# mobo_v2_0_6-20-18.net
KiCad netlist of a schematic drawn in EAGLE
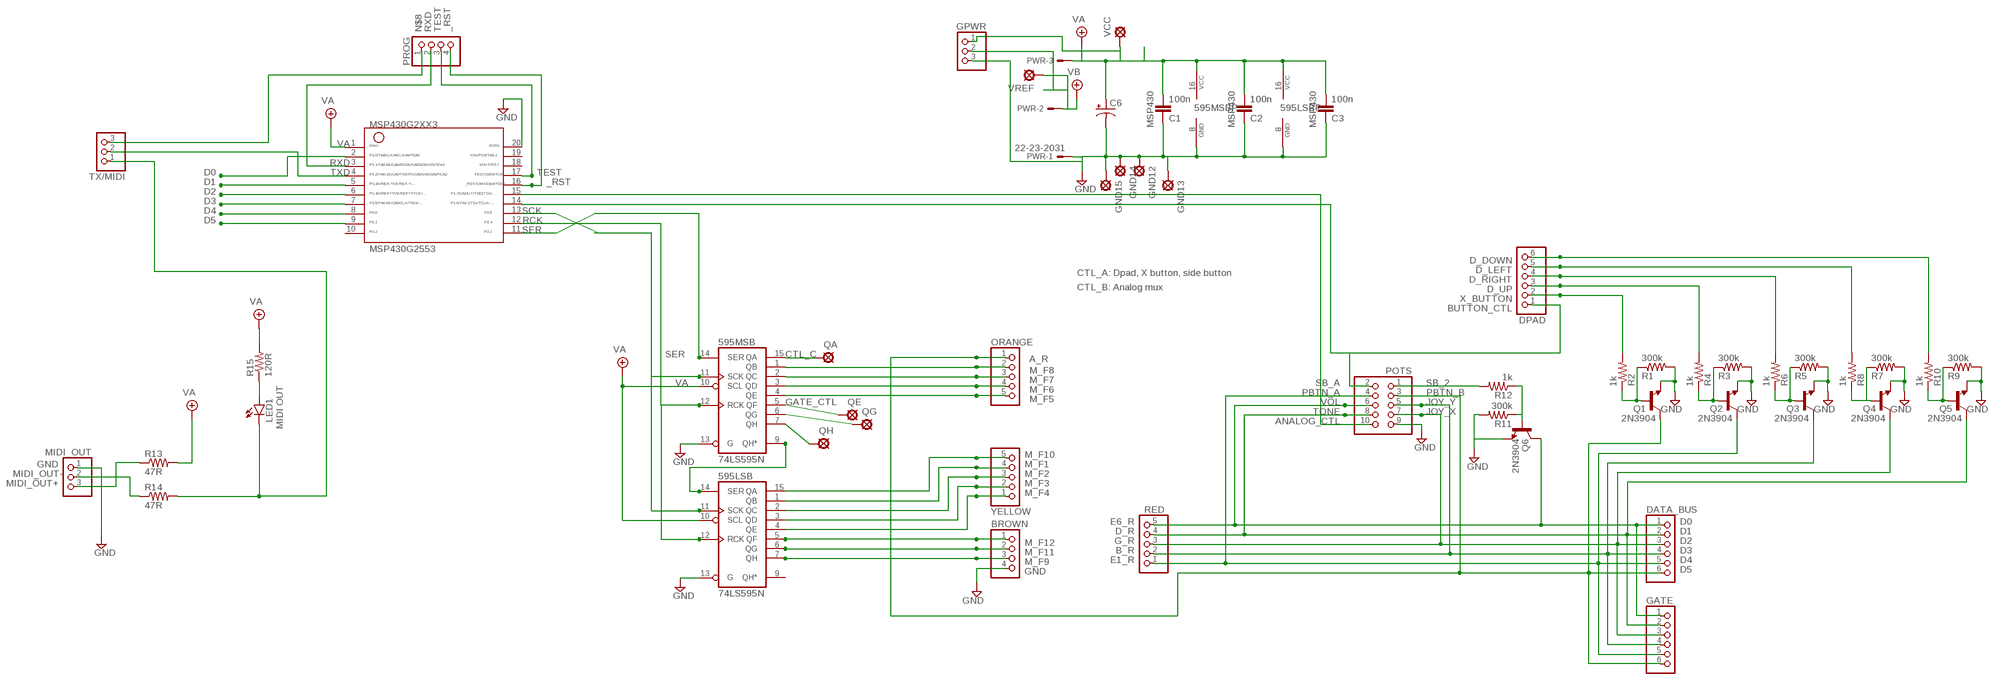
[diagram p0: schematic, sheet 1]

(export (version "E")
  (design (tool "Eeschema 10.0.6"))
  (components
    (comp (ref "595LSB")
      (value "74LS595N")
      (footprint "eagle-import:DIL16")
      (libsource (lib "eagle-import") (part "74595NLS"))
    )
    (comp (ref "595MSB")
      (value "74LS595N")
      (footprint "eagle-import:DIL16")
      (libsource (lib "eagle-import") (part "74595NLS"))
    )
    (comp (ref "BROWN")
      (value "PINHD-1X4")
      (footprint "eagle-import:1X04")
      (libsource (lib "eagle-import") (part "PINHD-1X4"))
    )
    (comp (ref "C1")
      (value "100n")
      (footprint "eagle-import:050X030_050_3")
      (libsource (lib "eagle-import") (part "050X030_050"))
    )
    (comp (ref "C2")
      (value "100n")
      (footprint "eagle-import:050X030_050_1")
      (libsource (lib "eagle-import") (part "050X030_0501"))
    )
    (comp (ref "C3")
      (value "100n")
      (footprint "eagle-import:050X030_050_1")
      (libsource (lib "eagle-import") (part "050X030_0501"))
    )
    (comp (ref "C6")
      (value "0501")
      (footprint "eagle-import:050_020_1")
      (libsource (lib "eagle-import") (part "0501"))
    )
    (comp (ref "DATA_BUS")
      (value "PINHD-1X6")
      (footprint "eagle-import:1X06")
      (libsource (lib "eagle-import") (part "PINHD-1X6"))
    )
    (comp (ref "DPAD")
      (value "PINHD-1X6")
      (footprint "eagle-import:1X06")
      (libsource (lib "eagle-import") (part "PINHD-1X6"))
    )
    (comp (ref "GATE")
      (value "PINHD-1X6")
      (footprint "eagle-import:1X06")
      (libsource (lib "eagle-import") (part "PINHD-1X6"))
    )
    (comp (ref "GND12")
      (value "PAD")
      (footprint "eagle-import:SQUARE")
      (libsource (lib "eagle-import") (part "PAD"))
    )
    (comp (ref "GND13")
      (value "PAD")
      (footprint "eagle-import:SQUARE")
      (libsource (lib "eagle-import") (part "PAD"))
    )
    (comp (ref "GND14")
      (value "PAD")
      (footprint "eagle-import:SQUARE")
      (libsource (lib "eagle-import") (part "PAD"))
    )
    (comp (ref "GND15")
      (value "PAD")
      (footprint "eagle-import:SQUARE")
      (libsource (lib "eagle-import") (part "PAD"))
    )
    (comp (ref "GPWR")
      (value "PINHD-1X3")
      (footprint "eagle-import:1X03")
      (libsource (lib "eagle-import") (part "PINHD-1X3"))
    )
    (comp (ref "LED1")
      (value "LED3MM")
      (footprint "eagle-import:LED3MM")
      (libsource (lib "eagle-import") (part "LED3MM"))
    )
    (comp (ref "MIDI_OUT")
      (value "PINHD-1X3")
      (footprint "eagle-import:1X03")
      (libsource (lib "eagle-import") (part "PINHD-1X3"))
    )
    (comp (ref "MSP430G2553")
      (value "G2XX3---N20")
      (footprint "eagle-import:N20")
      (libsource (lib "eagle-import") (part "G2XX3---N20"))
    )
    (comp (ref "ORANGE")
      (value "PINHD-1X5")
      (footprint "eagle-import:1X05")
      (libsource (lib "eagle-import") (part "PINHD-1X5"))
    )
    (comp (ref "POTS")
      (value "PINHD-2X5IDC")
      (footprint "eagle-import:10PIN_IDC")
      (libsource (lib "eagle-import") (part "PINHD-2X5IDC"))
    )
    (comp (ref "PROG")
      (value "PINHD-1X4")
      (footprint "eagle-import:1X04")
      (libsource (lib "eagle-import") (part "PINHD-1X4"))
    )
    (comp (ref "PWR")
      (value "22-23-2031")
      (footprint "eagle-import:22-23-2031")
      (fields (field (name "MF") "MOLEX"))
      (libsource (lib "eagle-import") (part "22-23-2031"))
    )
    (comp (ref "Q1")
      (value "2N3904")
      (footprint "eagle-import:TO92-")
      (libsource (lib "eagle-import") (part "2N3904"))
    )
    (comp (ref "Q2")
      (value "2N3904")
      (footprint "eagle-import:TO92-")
      (libsource (lib "eagle-import") (part "2N3904"))
    )
    (comp (ref "Q3")
      (value "2N3904")
      (footprint "eagle-import:TO92-")
      (libsource (lib "eagle-import") (part "2N3904"))
    )
    (comp (ref "Q4")
      (value "2N3904")
      (footprint "eagle-import:TO92-")
      (libsource (lib "eagle-import") (part "2N3904"))
    )
    (comp (ref "Q5")
      (value "2N3904")
      (footprint "eagle-import:TO92-")
      (libsource (lib "eagle-import") (part "2N3904"))
    )
    (comp (ref "Q6")
      (value "2N3904")
      (footprint "eagle-import:TO92-")
      (libsource (lib "eagle-import") (part "2N3904"))
    )
    (comp (ref "QA")
      (value "PAD")
      (footprint "eagle-import:SQUARE")
      (libsource (lib "eagle-import") (part "PAD"))
    )
    (comp (ref "QE")
      (value "PAD")
      (footprint "eagle-import:SQUARE")
      (libsource (lib "eagle-import") (part "PAD"))
    )
    (comp (ref "QG")
      (value "PAD")
      (footprint "eagle-import:SQUARE")
      (libsource (lib "eagle-import") (part "PAD"))
    )
    (comp (ref "QH")
      (value "PAD")
      (footprint "eagle-import:SQUARE")
      (libsource (lib "eagle-import") (part "PAD"))
    )
    (comp (ref "R1")
      (value "300k")
      (footprint "eagle-import:R0207_3")
      (libsource (lib "eagle-import") (part "6MM.3"))
    )
    (comp (ref "R2")
      (value "1k")
      (footprint "eagle-import:R0207_3")
      (libsource (lib "eagle-import") (part "6MM.3"))
    )
    (comp (ref "R3")
      (value "300k")
      (footprint "eagle-import:R0207_3")
      (libsource (lib "eagle-import") (part "6MM.3"))
    )
    (comp (ref "R4")
      (value "1k")
      (footprint "eagle-import:R0207_3")
      (libsource (lib "eagle-import") (part "6MM.3"))
    )
    (comp (ref "R5")
      (value "300k")
      (footprint "eagle-import:R0207_3")
      (libsource (lib "eagle-import") (part "6MM.3"))
    )
    (comp (ref "R6")
      (value "1k")
      (footprint "eagle-import:R0207_3")
      (libsource (lib "eagle-import") (part "6MM.3"))
    )
    (comp (ref "R7")
      (value "300k")
      (footprint "eagle-import:R0207_3")
      (libsource (lib "eagle-import") (part "6MM.3"))
    )
    (comp (ref "R8")
      (value "1k")
      (footprint "eagle-import:R0207_3")
      (libsource (lib "eagle-import") (part "6MM.3"))
    )
    (comp (ref "R9")
      (value "300k")
      (footprint "eagle-import:R0207_3")
      (libsource (lib "eagle-import") (part "6MM.3"))
    )
    (comp (ref "R10")
      (value "1k")
      (footprint "eagle-import:R0207_3")
      (libsource (lib "eagle-import") (part "6MM.3"))
    )
    (comp (ref "R11")
      (value "300k")
      (footprint "eagle-import:R0207_3")
      (libsource (lib "eagle-import") (part "6MM.3"))
    )
    (comp (ref "R12")
      (value "1k")
      (footprint "eagle-import:R0207_3")
      (libsource (lib "eagle-import") (part "6MM.3"))
    )
    (comp (ref "R13")
      (value "47R")
      (footprint "eagle-import:R0207_3")
      (libsource (lib "eagle-import") (part "6MM.3"))
    )
    (comp (ref "R14")
      (value "47R")
      (footprint "eagle-import:R0207_3")
      (libsource (lib "eagle-import") (part "6MM.3"))
    )
    (comp (ref "R15")
      (value "120R")
      (footprint "eagle-import:R0207_3")
      (libsource (lib "eagle-import") (part "6MM.3"))
    )
    (comp (ref "RED")
      (value "PINHD-1X5")
      (footprint "eagle-import:1X05")
      (libsource (lib "eagle-import") (part "PINHD-1X5"))
    )
    (comp (ref "TX/MIDI")
      (value "PINHD-1X3")
      (footprint "eagle-import:1X03")
      (libsource (lib "eagle-import") (part "PINHD-1X3"))
    )
    (comp (ref "VCC")
      (value "PAD")
      (footprint "eagle-import:SQUARE")
      (libsource (lib "eagle-import") (part "PAD"))
    )
    (comp (ref "VREF")
      (value "PAD")
      (footprint "eagle-import:SQUARE")
      (libsource (lib "eagle-import") (part "PAD"))
    )
    (comp (ref "YELLOW")
      (value "PINHD-1X5")
      (footprint "eagle-import:1X05")
      (libsource (lib "eagle-import") (part "PINHD-1X5"))
    )
  )
  (nets
    (net (code "1") (name "/ANALOG_CTL") (class "Default")
      (node (ref "MSP430G2553") (pin "15") (pinfunction "15_15") (pintype "bidirectional"))
      (node (ref "POTS") (pin "10") (pinfunction "10_10") (pintype "passive"))
    )
    (net (code "2") (name "/BUTTON_CTL") (class "Default")
      (node (ref "DPAD") (pin "1") (pinfunction "1_1") (pintype "passive"))
      (node (ref "MSP430G2553") (pin "14") (pinfunction "14_14") (pintype "bidirectional"))
      (node (ref "POTS") (pin "2") (pinfunction "2_2") (pintype "passive"))
    )
    (net (code "3") (name "/CTL_C") (class "Default")
      (node (ref "595MSB") (pin "15") (pinfunction "QA_15") (pintype "tri_state"))
      (node (ref "QA") (pin "1") (pinfunction "PAD_1") (pintype "passive"))
    )
    (net (code "4") (name "/D0") (class "Default")
      (node (ref "DATA_BUS") (pin "1") (pinfunction "1_1") (pintype "passive"))
      (node (ref "GATE") (pin "1") (pinfunction "1_1") (pintype "passive"))
      (node (ref "MSP430G2553") (pin "2") (pinfunction "2_2") (pintype "bidirectional"))
      (node (ref "POTS") (pin "6") (pinfunction "6_6") (pintype "passive"))
      (node (ref "Q6") (pin "1") (pinfunction "C_1") (pintype "passive"))
      (node (ref "RED") (pin "5") (pinfunction "5_5") (pintype "passive"))
    )
    (net (code "5") (name "/D1") (class "Default")
      (node (ref "DATA_BUS") (pin "2") (pinfunction "2_2") (pintype "passive"))
      (node (ref "GATE") (pin "2") (pinfunction "2_2") (pintype "passive"))
      (node (ref "MSP430G2553") (pin "5") (pinfunction "5_5") (pintype "bidirectional"))
      (node (ref "POTS") (pin "8") (pinfunction "8_8") (pintype "passive"))
      (node (ref "Q5") (pin "1") (pinfunction "C_1") (pintype "passive"))
      (node (ref "RED") (pin "4") (pinfunction "4_4") (pintype "passive"))
    )
    (net (code "6") (name "/D2") (class "Default")
      (node (ref "DATA_BUS") (pin "3") (pinfunction "3_3") (pintype "passive"))
      (node (ref "GATE") (pin "3") (pinfunction "3_3") (pintype "passive"))
      (node (ref "MSP430G2553") (pin "6") (pinfunction "6_6") (pintype "bidirectional"))
      (node (ref "POTS") (pin "7") (pinfunction "7_7") (pintype "passive"))
      (node (ref "Q4") (pin "1") (pinfunction "C_1") (pintype "passive"))
      (node (ref "RED") (pin "3") (pinfunction "3_3") (pintype "passive"))
    )
    (net (code "7") (name "/D3") (class "Default")
      (node (ref "DATA_BUS") (pin "4") (pinfunction "4_4") (pintype "passive"))
      (node (ref "GATE") (pin "4") (pinfunction "4_4") (pintype "passive"))
      (node (ref "MSP430G2553") (pin "7") (pinfunction "7_7") (pintype "bidirectional"))
      (node (ref "POTS") (pin "5") (pinfunction "5_5") (pintype "passive"))
      (node (ref "Q3") (pin "1") (pinfunction "C_1") (pintype "passive"))
      (node (ref "RED") (pin "2") (pinfunction "2_2") (pintype "passive"))
    )
    (net (code "8") (name "/D4") (class "Default")
      (node (ref "DATA_BUS") (pin "5") (pinfunction "5_5") (pintype "passive"))
      (node (ref "GATE") (pin "5") (pinfunction "5_5") (pintype "passive"))
      (node (ref "MSP430G2553") (pin "8") (pinfunction "8_8") (pintype "bidirectional"))
      (node (ref "POTS") (pin "4") (pinfunction "4_4") (pintype "passive"))
      (node (ref "Q2") (pin "1") (pinfunction "C_1") (pintype "passive"))
      (node (ref "RED") (pin "1") (pinfunction "1_1") (pintype "passive"))
    )
    (net (code "9") (name "/D5") (class "Default")
      (node (ref "DATA_BUS") (pin "6") (pinfunction "6_6") (pintype "passive"))
      (node (ref "GATE") (pin "6") (pinfunction "6_6") (pintype "passive"))
      (node (ref "MSP430G2553") (pin "9") (pinfunction "9_9") (pintype "bidirectional"))
      (node (ref "ORANGE") (pin "1") (pinfunction "1_1") (pintype "passive"))
      (node (ref "POTS") (pin "3") (pinfunction "3_3") (pintype "passive"))
      (node (ref "Q1") (pin "1") (pinfunction "C_1") (pintype "passive"))
    )
    (net (code "10") (name "/D_DOWN") (class "Default")
      (node (ref "DPAD") (pin "6") (pinfunction "6_6") (pintype "passive"))
      (node (ref "R10") (pin "2") (pinfunction "2_2") (pintype "passive"))
    )
    (net (code "11") (name "/D_LEFT") (class "Default")
      (node (ref "DPAD") (pin "5") (pinfunction "5_5") (pintype "passive"))
      (node (ref "R8") (pin "2") (pinfunction "2_2") (pintype "passive"))
    )
    (net (code "12") (name "/D_RIGHT") (class "Default")
      (node (ref "DPAD") (pin "4") (pinfunction "4_4") (pintype "passive"))
      (node (ref "R6") (pin "2") (pinfunction "2_2") (pintype "passive"))
    )
    (net (code "13") (name "/D_UP") (class "Default")
      (node (ref "DPAD") (pin "3") (pinfunction "3_3") (pintype "passive"))
      (node (ref "R4") (pin "2") (pinfunction "2_2") (pintype "passive"))
    )
    (net (code "14") (name "/GATE_CTL") (class "Default")
      (node (ref "595MSB") (pin "5") (pinfunction "QF_5") (pintype "tri_state"))
      (node (ref "QE") (pin "1") (pinfunction "PAD_1") (pintype "passive"))
    )
    (net (code "15") (name "/MIDI_OUT+") (class "Default")
      (node (ref "MIDI_OUT") (pin "3") (pinfunction "3_3") (pintype "passive"))
      (node (ref "R13") (pin "1") (pinfunction "1_1") (pintype "passive"))
    )
    (net (code "16") (name "/MIDI_OUT-") (class "Default")
      (node (ref "MIDI_OUT") (pin "2") (pinfunction "2_2") (pintype "passive"))
      (node (ref "R14") (pin "1") (pinfunction "1_1") (pintype "passive"))
    )
    (net (code "17") (name "/M_F1") (class "Default")
      (node (ref "595LSB") (pin "1") (pinfunction "QB_1") (pintype "tri_state"))
      (node (ref "YELLOW") (pin "4") (pinfunction "4_4") (pintype "passive"))
    )
    (net (code "18") (name "/M_F2") (class "Default")
      (node (ref "595LSB") (pin "2") (pinfunction "QC_2") (pintype "tri_state"))
      (node (ref "YELLOW") (pin "3") (pinfunction "3_3") (pintype "passive"))
    )
    (net (code "19") (name "/M_F3") (class "Default")
      (node (ref "595LSB") (pin "3") (pinfunction "QD_3") (pintype "tri_state"))
      (node (ref "YELLOW") (pin "2") (pinfunction "2_2") (pintype "passive"))
    )
    (net (code "20") (name "/M_F4") (class "Default")
      (node (ref "595LSB") (pin "4") (pinfunction "QE_4") (pintype "tri_state"))
      (node (ref "YELLOW") (pin "1") (pinfunction "1_1") (pintype "passive"))
    )
    (net (code "21") (name "/M_F5") (class "Default")
      (node (ref "595MSB") (pin "4") (pinfunction "QE_4") (pintype "tri_state"))
      (node (ref "ORANGE") (pin "5") (pinfunction "5_5") (pintype "passive"))
    )
    (net (code "22") (name "/M_F6") (class "Default")
      (node (ref "595MSB") (pin "3") (pinfunction "QD_3") (pintype "tri_state"))
      (node (ref "ORANGE") (pin "4") (pinfunction "4_4") (pintype "passive"))
    )
    (net (code "23") (name "/M_F7") (class "Default")
      (node (ref "595MSB") (pin "2") (pinfunction "QC_2") (pintype "tri_state"))
      (node (ref "ORANGE") (pin "3") (pinfunction "3_3") (pintype "passive"))
    )
    (net (code "24") (name "/M_F8") (class "Default")
      (node (ref "595MSB") (pin "1") (pinfunction "QB_1") (pintype "tri_state"))
      (node (ref "ORANGE") (pin "2") (pinfunction "2_2") (pintype "passive"))
    )
    (net (code "25") (name "/M_F9") (class "Default")
      (node (ref "595LSB") (pin "7") (pinfunction "QH_7") (pintype "tri_state"))
      (node (ref "BROWN") (pin "3") (pinfunction "3_3") (pintype "passive"))
    )
    (net (code "26") (name "/M_F10") (class "Default")
      (node (ref "595LSB") (pin "15") (pinfunction "QA_15") (pintype "tri_state"))
      (node (ref "YELLOW") (pin "5") (pinfunction "5_5") (pintype "passive"))
    )
    (net (code "27") (name "/M_F11") (class "Default")
      (node (ref "595LSB") (pin "6") (pinfunction "QG_6") (pintype "tri_state"))
      (node (ref "BROWN") (pin "2") (pinfunction "2_2") (pintype "passive"))
    )
    (net (code "28") (name "/M_F12") (class "Default")
      (node (ref "595LSB") (pin "5") (pinfunction "QF_5") (pintype "tri_state"))
      (node (ref "BROWN") (pin "1") (pinfunction "1_1") (pintype "passive"))
    )
    (net (code "29") (name "/N$8") (class "Default")
      (node (ref "PROG") (pin "1") (pinfunction "1_1") (pintype "passive"))
      (node (ref "TX/MIDI") (pin "3") (pinfunction "3_3") (pintype "passive"))
    )
    (net (code "30") (name "/RCK") (class "Default")
      (node (ref "595LSB") (pin "12") (pinfunction "RCK_12") (pintype "input"))
      (node (ref "595MSB") (pin "12") (pinfunction "RCK_12") (pintype "input"))
      (node (ref "MSP430G2553") (pin "12") (pinfunction "12_12") (pintype "bidirectional"))
    )
    (net (code "31") (name "/RXD") (class "Default")
      (node (ref "MSP430G2553") (pin "3") (pinfunction "3_3") (pintype "bidirectional"))
      (node (ref "PROG") (pin "2") (pinfunction "2_2") (pintype "passive"))
    )
    (net (code "32") (name "/SB_2") (class "Default")
      (node (ref "POTS") (pin "1") (pinfunction "1_1") (pintype "passive"))
      (node (ref "R12") (pin "2") (pinfunction "2_2") (pintype "passive"))
    )
    (net (code "33") (name "/SCK") (class "Default")
      (node (ref "595LSB") (pin "11") (pinfunction "SCK_11") (pintype "input"))
      (node (ref "595MSB") (pin "11") (pinfunction "SCK_11") (pintype "input"))
      (node (ref "MSP430G2553") (pin "13") (pinfunction "13_13") (pintype "bidirectional"))
    )
    (net (code "34") (name "/SER") (class "Default")
      (node (ref "595MSB") (pin "14") (pinfunction "SER_14") (pintype "input"))
      (node (ref "MSP430G2553") (pin "11") (pinfunction "11_11") (pintype "bidirectional"))
    )
    (net (code "35") (name "/TEST") (class "Default")
      (node (ref "MSP430G2553") (pin "17") (pinfunction "17_17") (pintype "bidirectional"))
      (node (ref "PROG") (pin "3") (pinfunction "3_3") (pintype "passive"))
    )
    (net (code "36") (name "/TXD") (class "Default")
      (node (ref "MSP430G2553") (pin "4") (pinfunction "4_4") (pintype "bidirectional"))
      (node (ref "TX/MIDI") (pin "2") (pinfunction "2_2") (pintype "passive"))
    )
    (net (code "37") (name "/X_BUTTON") (class "Default")
      (node (ref "DPAD") (pin "2") (pinfunction "2_2") (pintype "passive"))
      (node (ref "R2") (pin "2") (pinfunction "2_2") (pintype "passive"))
    )
    (net (code "38") (name "/_RST") (class "Default")
      (node (ref "MSP430G2553") (pin "16") (pinfunction "16_16") (pintype "bidirectional"))
      (node (ref "PROG") (pin "4") (pinfunction "4_4") (pintype "passive"))
    )
    (net (code "39") (name "GND") (class "Default")
      (node (ref "595LSB") (pin "13") (pinfunction "G_13") (pintype "input"))
      (node (ref "595LSB") (pin "8") (pinfunction "GND_8") (pintype "power_in"))
      (node (ref "595MSB") (pin "13") (pinfunction "G_13") (pintype "input"))
      (node (ref "595MSB") (pin "8") (pinfunction "GND_8") (pintype "power_in"))
      (node (ref "BROWN") (pin "4") (pinfunction "4_4") (pintype "passive"))
      (node (ref "C1") (pin "1") (pinfunction "1_1") (pintype "passive"))
      (node (ref "C2") (pin "1") (pinfunction "1_1") (pintype "passive"))
      (node (ref "C3") (pin "1") (pinfunction "1_1") (pintype "passive"))
      (node (ref "C6") (pin "-") (pinfunction "-_-") (pintype "passive"))
      (node (ref "GND12") (pin "1") (pinfunction "PAD_1") (pintype "passive"))
      (node (ref "GND13") (pin "1") (pinfunction "PAD_1") (pintype "passive"))
      (node (ref "GND14") (pin "1") (pinfunction "PAD_1") (pintype "passive"))
      (node (ref "GND15") (pin "1") (pinfunction "PAD_1") (pintype "passive"))
      (node (ref "GPWR") (pin "3") (pinfunction "3_3") (pintype "passive"))
      (node (ref "MIDI_OUT") (pin "1") (pinfunction "1_1") (pintype "passive"))
      (node (ref "MSP430G2553") (pin "20") (pinfunction "20_20") (pintype "bidirectional"))
      (node (ref "POTS") (pin "9") (pinfunction "9_9") (pintype "passive"))
      (node (ref "PWR") (pin "1") (pinfunction "S_1") (pintype "passive"))
      (node (ref "Q1") (pin "3") (pinfunction "E_3") (pintype "passive"))
      (node (ref "Q2") (pin "3") (pinfunction "E_3") (pintype "passive"))
      (node (ref "Q3") (pin "3") (pinfunction "E_3") (pintype "passive"))
      (node (ref "Q4") (pin "3") (pinfunction "E_3") (pintype "passive"))
      (node (ref "Q5") (pin "3") (pinfunction "E_3") (pintype "passive"))
      (node (ref "Q6") (pin "3") (pinfunction "E_3") (pintype "passive"))
      (node (ref "R1") (pin "2") (pinfunction "2_2") (pintype "passive"))
      (node (ref "R11") (pin "2") (pinfunction "2_2") (pintype "passive"))
      (node (ref "R3") (pin "2") (pinfunction "2_2") (pintype "passive"))
      (node (ref "R5") (pin "2") (pinfunction "2_2") (pintype "passive"))
      (node (ref "R7") (pin "2") (pinfunction "2_2") (pintype "passive"))
      (node (ref "R9") (pin "2") (pinfunction "2_2") (pintype "passive"))
    )
    (net (code "40") (name "Net-(595LSBA-SER)") (class "Default")
      (node (ref "595LSB") (pin "14") (pinfunction "SER_14") (pintype "input"))
      (node (ref "595MSB") (pin "9") (pinfunction "QH*_9") (pintype "tri_state"))
    )
    (net (code "41") (name "Net-(595MSBA-QG)") (class "Default")
      (node (ref "595MSB") (pin "6") (pinfunction "QG_6") (pintype "tri_state"))
      (node (ref "QG") (pin "1") (pinfunction "PAD_1") (pintype "passive"))
    )
    (net (code "42") (name "Net-(595MSBA-QH)") (class "Default")
      (node (ref "595MSB") (pin "7") (pinfunction "QH_7") (pintype "tri_state"))
      (node (ref "QH") (pin "1") (pinfunction "PAD_1") (pintype "passive"))
    )
    (net (code "43") (name "Net-(LED1-C)") (class "Default")
      (node (ref "LED1") (pin "K") (pinfunction "C_K") (pintype "passive"))
      (node (ref "R14") (pin "2") (pinfunction "2_2") (pintype "passive"))
      (node (ref "TX/MIDI") (pin "1") (pinfunction "1_1") (pintype "passive"))
    )
    (net (code "44") (name "Net-(LED1-PadA)") (class "Default")
      (node (ref "LED1") (pin "A") (pinfunction "A_A") (pintype "passive"))
      (node (ref "R15") (pin "1") (pinfunction "1_1") (pintype "passive"))
    )
    (net (code "45") (name "Net-(Q1-B)") (class "Default")
      (node (ref "Q1") (pin "2") (pinfunction "B_2") (pintype "passive"))
      (node (ref "R1") (pin "1") (pinfunction "1_1") (pintype "passive"))
      (node (ref "R2") (pin "1") (pinfunction "1_1") (pintype "passive"))
    )
    (net (code "46") (name "Net-(Q2-B)") (class "Default")
      (node (ref "Q2") (pin "2") (pinfunction "B_2") (pintype "passive"))
      (node (ref "R3") (pin "1") (pinfunction "1_1") (pintype "passive"))
      (node (ref "R4") (pin "1") (pinfunction "1_1") (pintype "passive"))
    )
    (net (code "47") (name "Net-(Q3-B)") (class "Default")
      (node (ref "Q3") (pin "2") (pinfunction "B_2") (pintype "passive"))
      (node (ref "R5") (pin "1") (pinfunction "1_1") (pintype "passive"))
      (node (ref "R6") (pin "1") (pinfunction "1_1") (pintype "passive"))
    )
    (net (code "48") (name "Net-(Q4-B)") (class "Default")
      (node (ref "Q4") (pin "2") (pinfunction "B_2") (pintype "passive"))
      (node (ref "R7") (pin "1") (pinfunction "1_1") (pintype "passive"))
      (node (ref "R8") (pin "1") (pinfunction "1_1") (pintype "passive"))
    )
    (net (code "49") (name "Net-(Q5-B)") (class "Default")
      (node (ref "Q5") (pin "2") (pinfunction "B_2") (pintype "passive"))
      (node (ref "R10") (pin "1") (pinfunction "1_1") (pintype "passive"))
      (node (ref "R9") (pin "1") (pinfunction "1_1") (pintype "passive"))
    )
    (net (code "50") (name "Net-(Q6-B)") (class "Default")
      (node (ref "Q6") (pin "2") (pinfunction "B_2") (pintype "passive"))
      (node (ref "R11") (pin "1") (pinfunction "1_1") (pintype "passive"))
      (node (ref "R12") (pin "1") (pinfunction "1_1") (pintype "passive"))
    )
    (net (code "51") (name "VA") (class "Default")
      (node (ref "595LSB") (pin "10") (pinfunction "SCL_10") (pintype "input"))
      (node (ref "595LSB") (pin "16") (pinfunction "VCC_16") (pintype "power_in"))
      (node (ref "595MSB") (pin "10") (pinfunction "SCL_10") (pintype "input"))
      (node (ref "595MSB") (pin "16") (pinfunction "VCC_16") (pintype "power_in"))
      (node (ref "C1") (pin "2") (pinfunction "2_2") (pintype "passive"))
      (node (ref "C2") (pin "2") (pinfunction "2_2") (pintype "passive"))
      (node (ref "C3") (pin "2") (pinfunction "2_2") (pintype "passive"))
      (node (ref "C6") (pin "+") (pinfunction "+_+") (pintype "passive"))
      (node (ref "GPWR") (pin "1") (pinfunction "1_1") (pintype "passive"))
      (node (ref "MSP430G2553") (pin "1") (pinfunction "1_1") (pintype "bidirectional"))
      (node (ref "PWR") (pin "3") (pinfunction "S_3") (pintype "passive"))
      (node (ref "R13") (pin "2") (pinfunction "2_2") (pintype "passive"))
      (node (ref "R15") (pin "2") (pinfunction "2_2") (pintype "passive"))
      (node (ref "VCC") (pin "1") (pinfunction "PAD_1") (pintype "passive"))
    )
    (net (code "52") (name "VB") (class "Default")
      (node (ref "GPWR") (pin "2") (pinfunction "2_2") (pintype "passive"))
      (node (ref "PWR") (pin "2") (pinfunction "S_2") (pintype "passive"))
      (node (ref "VREF") (pin "1") (pinfunction "PAD_1") (pintype "passive"))
    )
    (net (code "53") (name "unconnected-(595LSBA-QH*-Pad9)") (class "Default")
      (node (ref "595LSB") (pin "9") (pinfunction "QH*_9") (pintype "tri_state"))
    )
    (net (code "54") (name "unconnected-(MSP430G2553-Pad10)") (class "Default")
      (node (ref "MSP430G2553") (pin "10") (pinfunction "10_10") (pintype "bidirectional"))
    )
    (net (code "55") (name "unconnected-(MSP430G2553-Pad18)") (class "Default")
      (node (ref "MSP430G2553") (pin "18") (pinfunction "18_18") (pintype "bidirectional"))
    )
    (net (code "56") (name "unconnected-(MSP430G2553-Pad19)") (class "Default")
      (node (ref "MSP430G2553") (pin "19") (pinfunction "19_19") (pintype "bidirectional"))
    )
  )
)
